# sensores.net
KiCad netlist of a schematic drawn in EAGLE
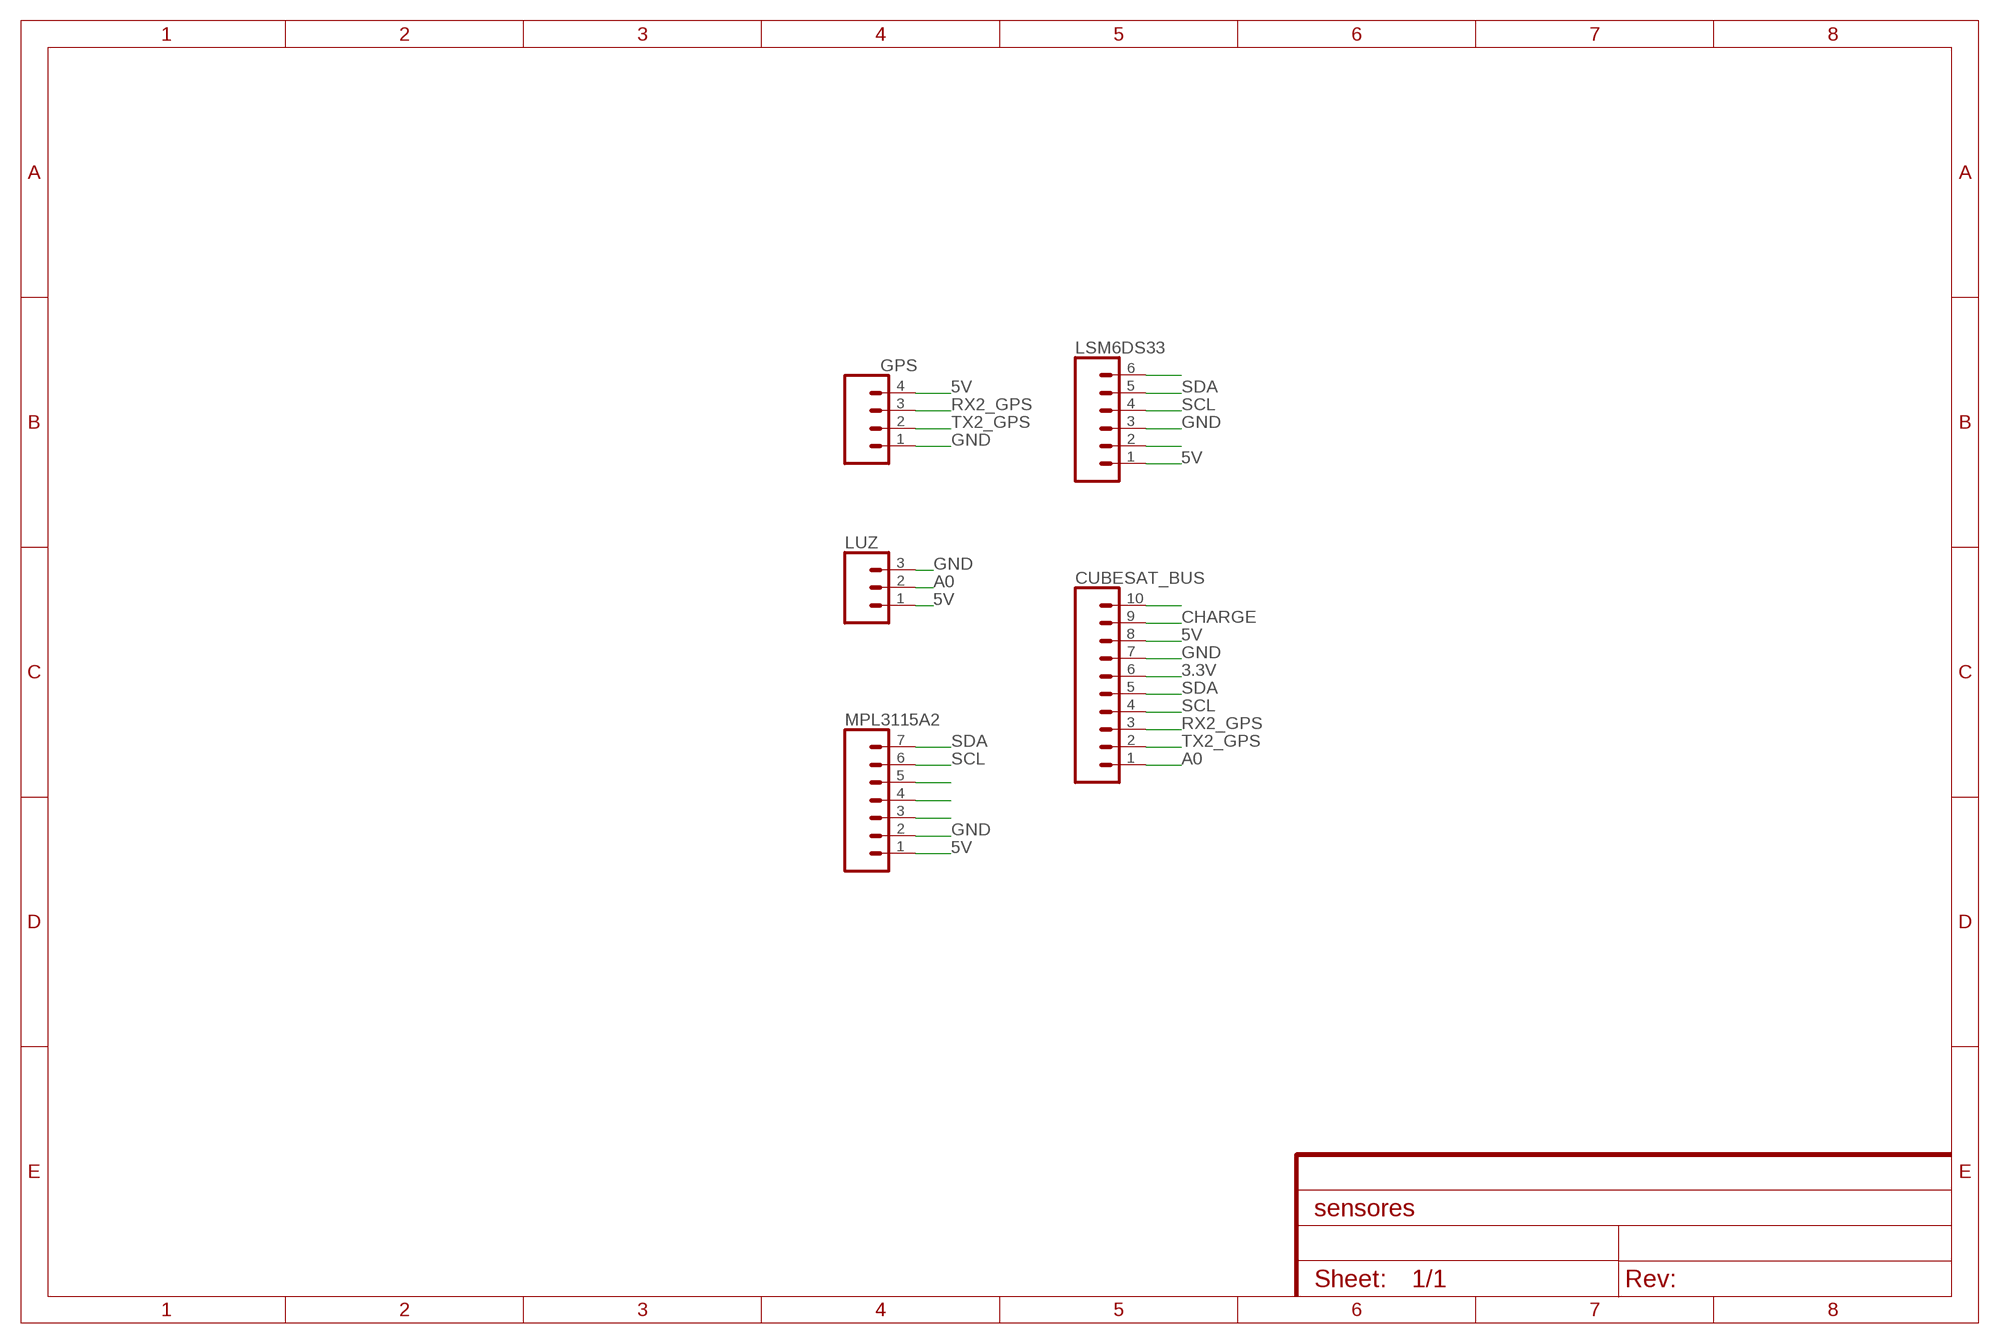
[diagram p0: schematic, sheet 1]

(export (version "E")
  (design (tool "Eeschema 10.0.6"))
  (components
    (comp (ref "CUBESAT_BUS")
      (value "CONN_10\"")
      (footprint "eagle-import:1X10")
      (libsource (lib "eagle-import") (part "CONN_10{dblquote}"))
    )
    (comp (ref "GPS")
      (value "CONN_04")
      (footprint "eagle-import:1X04")
      (libsource (lib "eagle-import") (part "CONN_04"))
    )
    (comp (ref "LSM6DS33")
      (value "CONN_06SILK_FEMALE_PTH")
      (footprint "eagle-import:1X06")
      (libsource (lib "eagle-import") (part "CONN_06SILK_FEMALE_PTH"))
    )
    (comp (ref "LUZ")
      (value "CONN_03")
      (footprint "eagle-import:1X03")
      (libsource (lib "eagle-import") (part "CONN_03"))
    )
    (comp (ref "MPL3115A2")
      (value "CONN_07")
      (footprint "eagle-import:1X07")
      (libsource (lib "eagle-import") (part "CONN_07"))
    )
  )
  (nets
    (net (code "1") (name "/3.3V") (class "Default")
      (node (ref "CUBESAT_BUS") (pin "6") (pinfunction "6_6") (pintype "passive"))
    )
    (net (code "2") (name "/5V") (class "Default")
      (node (ref "CUBESAT_BUS") (pin "8") (pinfunction "8_8") (pintype "passive"))
      (node (ref "GPS") (pin "4") (pinfunction "4_4") (pintype "passive"))
      (node (ref "LSM6DS33") (pin "1") (pinfunction "1_1") (pintype "passive"))
      (node (ref "LUZ") (pin "1") (pinfunction "1_1") (pintype "passive"))
      (node (ref "MPL3115A2") (pin "1") (pinfunction "1_1") (pintype "passive"))
    )
    (net (code "3") (name "/A0") (class "Default")
      (node (ref "CUBESAT_BUS") (pin "1") (pinfunction "1_1") (pintype "passive"))
      (node (ref "LUZ") (pin "2") (pinfunction "2_2") (pintype "passive"))
    )
    (net (code "4") (name "/CHARGE") (class "Default")
      (node (ref "CUBESAT_BUS") (pin "9") (pinfunction "9_9") (pintype "passive"))
    )
    (net (code "5") (name "/GND") (class "Default")
      (node (ref "CUBESAT_BUS") (pin "7") (pinfunction "7_7") (pintype "passive"))
      (node (ref "GPS") (pin "1") (pinfunction "1_1") (pintype "passive"))
      (node (ref "LSM6DS33") (pin "3") (pinfunction "3_3") (pintype "passive"))
      (node (ref "LUZ") (pin "3") (pinfunction "3_3") (pintype "passive"))
      (node (ref "MPL3115A2") (pin "2") (pinfunction "2_2") (pintype "passive"))
    )
    (net (code "6") (name "/RX2_GPS") (class "Default")
      (node (ref "CUBESAT_BUS") (pin "3") (pinfunction "3_3") (pintype "passive"))
      (node (ref "GPS") (pin "3") (pinfunction "3_3") (pintype "passive"))
    )
    (net (code "7") (name "/SCL") (class "Default")
      (node (ref "CUBESAT_BUS") (pin "4") (pinfunction "4_4") (pintype "passive"))
      (node (ref "LSM6DS33") (pin "4") (pinfunction "4_4") (pintype "passive"))
      (node (ref "MPL3115A2") (pin "6") (pinfunction "6_6") (pintype "passive"))
    )
    (net (code "8") (name "/SDA") (class "Default")
      (node (ref "CUBESAT_BUS") (pin "5") (pinfunction "5_5") (pintype "passive"))
      (node (ref "LSM6DS33") (pin "5") (pinfunction "5_5") (pintype "passive"))
      (node (ref "MPL3115A2") (pin "7") (pinfunction "7_7") (pintype "passive"))
    )
    (net (code "9") (name "/TX2_GPS") (class "Default")
      (node (ref "CUBESAT_BUS") (pin "2") (pinfunction "2_2") (pintype "passive"))
      (node (ref "GPS") (pin "2") (pinfunction "2_2") (pintype "passive"))
    )
    (net (code "10") (name "unconnected-(CUBESAT_BUS-Pad10)") (class "Default")
      (node (ref "CUBESAT_BUS") (pin "10") (pinfunction "10_10") (pintype "passive"))
    )
    (net (code "11") (name "unconnected-(LSM6DS33-Pad2)") (class "Default")
      (node (ref "LSM6DS33") (pin "2") (pinfunction "2_2") (pintype "passive"))
    )
    (net (code "12") (name "unconnected-(LSM6DS33-Pad6)") (class "Default")
      (node (ref "LSM6DS33") (pin "6") (pinfunction "6_6") (pintype "passive"))
    )
    (net (code "13") (name "unconnected-(MPL3115A2-Pad3)") (class "Default")
      (node (ref "MPL3115A2") (pin "3") (pinfunction "3_3") (pintype "passive"))
    )
    (net (code "14") (name "unconnected-(MPL3115A2-Pad4)") (class "Default")
      (node (ref "MPL3115A2") (pin "4") (pinfunction "4_4") (pintype "passive"))
    )
    (net (code "15") (name "unconnected-(MPL3115A2-Pad5)") (class "Default")
      (node (ref "MPL3115A2") (pin "5") (pinfunction "5_5") (pintype "passive"))
    )
  )
)
